# radio_frequency.net
KiCad netlist of a schematic drawn in Altium Designer
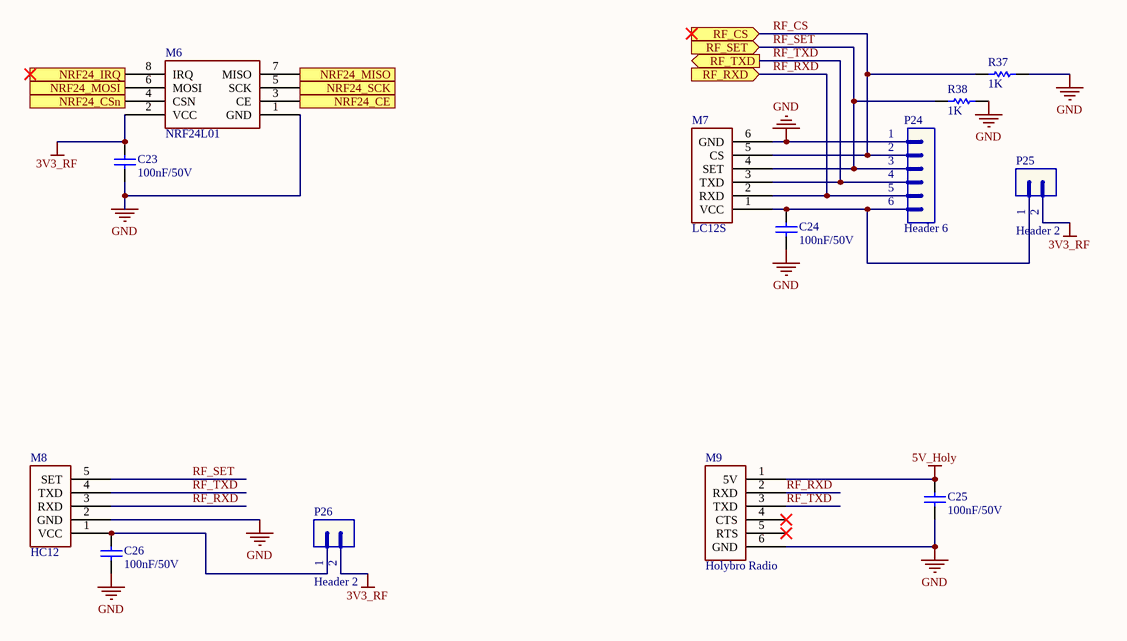
[diagram p0: radio_frequency.SchDoc]

(export (version "E")
  (design (tool "Eeschema 10.0.6"))
  (components
    (comp (ref "C23")
      (value "100nF/50V")
      (footprint "CAP-SM-0805")
      (description "CAP CER 0.1UF 50V Y5V 0805")
      (fields
        (field (name "MANUFACTURER") "Samsung Electro-Mechanics")
        (field (name "MANUFACTURER PART NUMBER") "CL21F104ZBCNNNC")
      )
      (libsource (lib "Capacitor") (part "Cap-100nF-50V-0805"))
    )
    (comp (ref "C24")
      (value "100nF/50V")
      (footprint "CAP-SM-0805")
      (description "CAP CER 0.1UF 50V Y5V 0805")
      (fields
        (field (name "MANUFACTURER") "Samsung Electro-Mechanics")
        (field (name "MANUFACTURER PART NUMBER") "CL21F104ZBCNNNC")
      )
      (libsource (lib "Capacitor") (part "Cap-100nF-50V-0805"))
    )
    (comp (ref "C25")
      (value "100nF/50V")
      (footprint "CAP-SM-0805")
      (description "CAP CER 0.1UF 50V Y5V 0805")
      (fields
        (field (name "MANUFACTURER") "Samsung Electro-Mechanics")
        (field (name "MANUFACTURER PART NUMBER") "CL21F104ZBCNNNC")
      )
      (libsource (lib "Capacitor") (part "Cap-100nF-50V-0805"))
    )
    (comp (ref "C26")
      (value "100nF/50V")
      (footprint "CAP-SM-0805")
      (description "CAP CER 0.1UF 50V Y5V 0805")
      (fields
        (field (name "MANUFACTURER") "Samsung Electro-Mechanics")
        (field (name "MANUFACTURER PART NUMBER") "CL21F104ZBCNNNC")
      )
      (libsource (lib "Capacitor") (part "Cap-100nF-50V-0805"))
    )
    (comp (ref "M6")
      (value "NRF24L01")
      (footprint "NRF24L01")
      (libsource (lib "PIFWRobot") (part "NRF24L01"))
    )
    (comp (ref "M7") (value "LC12S") (footprint "LC12S") (libsource (lib "PIFWRobot") (part "LC12S")))
    (comp (ref "M8") (value "HC12") (footprint "HC12") (libsource (lib "PIFWRobot") (part "HC12")))
    (comp (ref "M9")
      (value "Holybro Radio")
      (footprint "HOLYBRO-RADIO")
      (fields (field (name "LOCAL SUPPLIER PART NUMBER") "x"))
      (libsource (lib "PIFWRobot") (part "Holybro Radio"))
    )
    (comp (ref "P24")
      (value "Header 6")
      (footprint "JP6")
      (description "Header, 6-Pin")
      (fields (field (name "LOCAL SUPPLIER PART NUMBER") "x") (field (name "PUBLISHER") "Altium Limited"))
      (libsource (lib "Header-Connector") (part "Header 6"))
    )
    (comp (ref "P25")
      (value "Header 2")
      (footprint "JP2")
      (description "Header, 2-Pin")
      (fields (field (name "LOCAL SUPPLIER PART NUMBER") "x") (field (name "PUBLISHER") "Altium Limited"))
      (libsource (lib "Header-Connector") (part "Header 2"))
    )
    (comp (ref "P26")
      (value "Header 2")
      (footprint "JP2")
      (description "Header, 2-Pin")
      (fields (field (name "LOCAL SUPPLIER PART NUMBER") "x") (field (name "PUBLISHER") "Altium Limited"))
      (libsource (lib "Header-Connector") (part "Header 2"))
    )
    (comp (ref "R37")
      (value "1K")
      (footprint "Resistor:RES-SM-0805")
      (description "RES 1K OHM 1% 1/4W 0805")
      (fields
        (field (name "MANUFACTURER") "Stackpole Electronics Inc")
        (field (name "MANUFACTURER PART NUMBER") "RNCP0805FTD1K00")
      )
      (libsource (lib "Resistor") (part "Res-1K-0805"))
    )
    (comp (ref "R38")
      (value "1K")
      (footprint "Resistor:RES-SM-0805")
      (description "RES 1K OHM 1% 1/4W 0805")
      (fields
        (field (name "MANUFACTURER") "Stackpole Electronics Inc")
        (field (name "MANUFACTURER PART NUMBER") "RNCP0805FTD1K00")
      )
      (libsource (lib "Resistor") (part "Res-1K-0805"))
    )
  )
  (nets
    (net (code "1") (name "/NRF24_CE") (class "Default")
      (node (ref "M6") (pin "3") (pinfunction "CE_3") (pintype "passive"))
    )
    (net (code "2") (name "/NRF24_CSn") (class "Default")
      (node (ref "M6") (pin "4") (pinfunction "CSN_4") (pintype "passive"))
    )
    (net (code "3") (name "/NRF24_IRQ") (class "Default")
      (node (ref "M6") (pin "8") (pinfunction "IRQ_8") (pintype "passive"))
    )
    (net (code "4") (name "/NRF24_MISO") (class "Default")
      (node (ref "M6") (pin "7") (pinfunction "MISO_7") (pintype "passive"))
    )
    (net (code "5") (name "/NRF24_MOSI") (class "Default")
      (node (ref "M6") (pin "6") (pinfunction "MOSI_6") (pintype "passive"))
    )
    (net (code "6") (name "/NRF24_SCK") (class "Default")
      (node (ref "M6") (pin "5") (pinfunction "SCK_5") (pintype "passive"))
    )
    (net (code "7") (name "/RF_CS") (class "Default")
      (node (ref "M7") (pin "5") (pinfunction "CS_5") (pintype "passive"))
      (node (ref "P24") (pin "2") (pinfunction "2_2") (pintype "passive"))
      (node (ref "R37") (pin "1") (pinfunction "1_1") (pintype "passive"))
    )
    (net (code "8") (name "/RF_RXD") (class "Default")
      (node (ref "M7") (pin "2") (pinfunction "RXD_2") (pintype "passive"))
      (node (ref "M8") (pin "3") (pinfunction "RXD_3") (pintype "passive"))
      (node (ref "M9") (pin "2") (pinfunction "RXD_2") (pintype "passive"))
      (node (ref "P24") (pin "5") (pinfunction "5_5") (pintype "passive"))
    )
    (net (code "9") (name "/RF_SET") (class "Default")
      (node (ref "M7") (pin "4") (pinfunction "SET_4") (pintype "passive"))
      (node (ref "M8") (pin "5") (pinfunction "SET_5") (pintype "passive"))
      (node (ref "P24") (pin "3") (pinfunction "3_3") (pintype "passive"))
      (node (ref "R38") (pin "1") (pinfunction "1_1") (pintype "passive"))
    )
    (net (code "10") (name "/RF_TXD") (class "Default")
      (node (ref "M7") (pin "3") (pinfunction "TXD_3") (pintype "passive"))
      (node (ref "M8") (pin "4") (pinfunction "TXD_4") (pintype "passive"))
      (node (ref "M9") (pin "3") (pinfunction "TXD_3") (pintype "passive"))
      (node (ref "P24") (pin "4") (pinfunction "4_4") (pintype "passive"))
    )
    (net (code "11") (name "3V3_RF") (class "Default")
      (node (ref "C23") (pin "2") (pinfunction "2_2") (pintype "passive"))
      (node (ref "M6") (pin "2") (pinfunction "VCC_2") (pintype "passive"))
      (node (ref "P25") (pin "2") (pinfunction "2_2") (pintype "passive"))
      (node (ref "P26") (pin "2") (pinfunction "2_2") (pintype "passive"))
    )
    (net (code "12") (name "5V_Holy") (class "Default")
      (node (ref "C25") (pin "2") (pinfunction "2_2") (pintype "passive"))
      (node (ref "M9") (pin "1") (pinfunction "5V_1") (pintype "passive"))
    )
    (net (code "13") (name "GND") (class "Default")
      (node (ref "C23") (pin "1") (pinfunction "1_1") (pintype "passive"))
      (node (ref "C24") (pin "1") (pinfunction "1_1") (pintype "passive"))
      (node (ref "C25") (pin "1") (pinfunction "1_1") (pintype "passive"))
      (node (ref "C26") (pin "1") (pinfunction "1_1") (pintype "passive"))
      (node (ref "M6") (pin "1") (pinfunction "GND_1") (pintype "passive"))
      (node (ref "M7") (pin "6") (pinfunction "GND_6") (pintype "passive"))
      (node (ref "M8") (pin "2") (pinfunction "GND_2") (pintype "passive"))
      (node (ref "M9") (pin "6") (pinfunction "GND_6") (pintype "passive"))
      (node (ref "P24") (pin "1") (pinfunction "1_1") (pintype "passive"))
      (node (ref "R37") (pin "2") (pinfunction "2_2") (pintype "passive"))
      (node (ref "R38") (pin "2") (pinfunction "2_2") (pintype "passive"))
    )
    (net (code "14") (name "Net-(M7-VCC)") (class "Default")
      (node (ref "C24") (pin "2") (pinfunction "2_2") (pintype "passive"))
      (node (ref "M7") (pin "1") (pinfunction "VCC_1") (pintype "passive"))
      (node (ref "P24") (pin "6") (pinfunction "6_6") (pintype "passive"))
      (node (ref "P25") (pin "1") (pinfunction "1_1") (pintype "passive"))
    )
    (net (code "15") (name "Net-(M8-VCC)") (class "Default")
      (node (ref "C26") (pin "2") (pinfunction "2_2") (pintype "passive"))
      (node (ref "M8") (pin "1") (pinfunction "VCC_1") (pintype "passive"))
      (node (ref "P26") (pin "1") (pinfunction "1_1") (pintype "passive"))
    )
    (net (code "16") (name "unconnected-(M9-CTS-Pad4)") (class "Default")
      (node (ref "M9") (pin "4") (pinfunction "CTS_4") (pintype "passive+no_connect"))
    )
    (net (code "17") (name "unconnected-(M9-RTS-Pad5)") (class "Default")
      (node (ref "M9") (pin "5") (pinfunction "RTS_5") (pintype "passive+no_connect"))
    )
  )
)
